# HMC478-SCH.net
KiCad netlist of a schematic drawn in Altium Designer
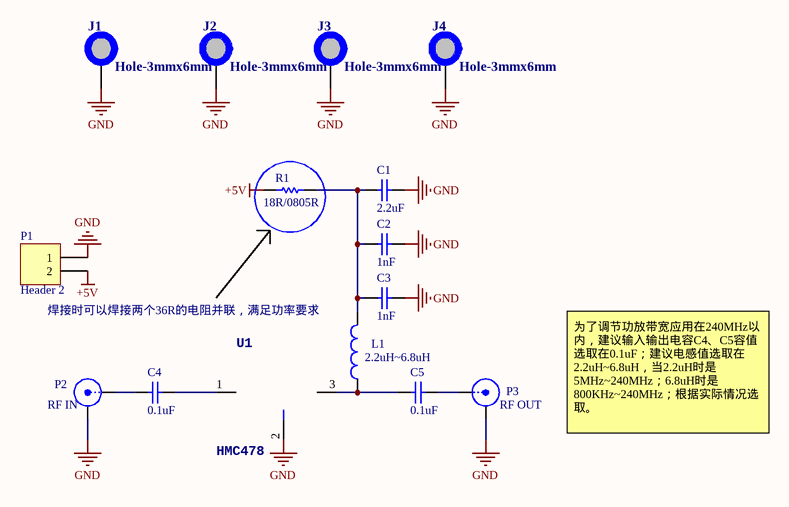
[diagram p0: HMC478-SCH.SchDoc]

(export (version "E")
  (design (tool "Eeschema 10.0.6"))
  (components
    (comp (ref "C1")
      (value "2.2uF")
      (footprint "1206T")
      (description "CAP CER 10000PF 100V X7R 0603")
      (fields
        (field (name "MANUFACTURER") "TDK Corporation")
        (field (name "MANUFACTURER PART NUMBER") "C1608X7R2A103K080AA")
      )
      (libsource (lib "Desiger_Schlib") (part "Cap1"))
    )
    (comp (ref "C2")
      (value "1nF")
      (footprint "0603C")
      (description "CAP CER 10000PF 100V X7R 0603")
      (fields
        (field (name "MANUFACTURER") "TDK Corporation")
        (field (name "MANUFACTURER PART NUMBER") "C1608X7R2A103K080AA")
      )
      (libsource (lib "Desiger_Schlib") (part "Cap1"))
    )
    (comp (ref "C3")
      (value "1nF")
      (footprint "0603C")
      (description "CAP CER 10000PF 100V X7R 0603")
      (fields
        (field (name "MANUFACTURER") "TDK Corporation")
        (field (name "MANUFACTURER PART NUMBER") "C1608X7R2A103K080AA")
      )
      (libsource (lib "Desiger_Schlib") (part "Cap1"))
    )
    (comp (ref "C4")
      (value "0.1uF")
      (footprint "0603C")
      (description "CAP CER 10000PF 100V X7R 0603")
      (fields
        (field (name "MANUFACTURER") "TDK Corporation")
        (field (name "MANUFACTURER PART NUMBER") "C1608X7R2A103K080AA")
      )
      (libsource (lib "Desiger_Schlib") (part "Cap1"))
    )
    (comp (ref "C5")
      (value "0.1uF")
      (footprint "0603C")
      (description "CAP CER 10000PF 100V X7R 0603")
      (fields
        (field (name "MANUFACTURER") "TDK Corporation")
        (field (name "MANUFACTURER PART NUMBER") "C1608X7R2A103K080AA")
      )
      (libsource (lib "Desiger_Schlib") (part "Cap1"))
    )
    (comp (ref "J1")
      (value "Hole-3mmx6mm")
      (footprint "Hole")
      (libsource (lib "Desiger_Schlib") (part "HOLED"))
    )
    (comp (ref "J2")
      (value "Hole-3mmx6mm")
      (footprint "Hole")
      (libsource (lib "Desiger_Schlib") (part "HOLED"))
    )
    (comp (ref "J3")
      (value "Hole-3mmx6mm")
      (footprint "Hole")
      (libsource (lib "Desiger_Schlib") (part "HOLED"))
    )
    (comp (ref "J4")
      (value "Hole-3mmx6mm")
      (footprint "Hole")
      (libsource (lib "Desiger_Schlib") (part "HOLED"))
    )
    (comp (ref "L1")
      (value "2.2uH~6.8uH")
      (footprint "0603L")
      (description "FIXED IND 240NH 4.4A 22MOHM SMD")
      (fields
        (field (name "MANUFACTURER") "Samsung Electro-Mechanics")
        (field (name "MANUFACTURER PART NUMBER") "CIGT201210UHR24MNE")
      )
      (libsource (lib "Desiger_Schlib") (part "Inductors"))
    )
    (comp (ref "P1")
      (value "Header 2")
      (footprint "KF2EDG_3R81_2P")
      (description "Header, 2-Pin")
      (fields (field (name "PUBLISHER") "Altium Limited"))
      (libsource (lib "Miscellaneous Connectors") (part "Header 2"))
    )
    (comp (ref "P2")
      (value "RF IN")
      (footprint "SMA-SMD")
      (description "BNC Elbow Connector")
      (fields (field (name "PUBLISHER") "Altium Limited"))
      (libsource (lib "Miscellaneous Connectors") (part "BNC"))
    )
    (comp (ref "P3")
      (value "RF OUT")
      (footprint "SMA-SMD")
      (description "BNC Elbow Connector")
      (fields (field (name "PUBLISHER") "Altium Limited"))
      (libsource (lib "Miscellaneous Connectors") (part "BNC"))
    )
    (comp (ref "R1")
      (value "18R/0805R")
      (footprint "0805R")
      (description "RES SMD 1K OHM 0.5% 1/16W 0603")
      (fields
        (field (name "MANUFACTURER") "Susumu")
        (field (name "MANUFACTURER PART NUMBER") "RR0816P-102-D")
      )
      (libsource (lib "Desiger_Schlib") (part "Res1"))
    )
    (comp (ref "U1")
      (value "HMC478")
      (footprint "SOT89")
      (description "SiGe HBT GAIN BLOCK  MMIC AMPLIFIER, DC - 4 GHz")
      (libsource (lib "Desiger_Schlib") (part "HMC478"))
    )
  )
  (nets
    (net (code "1") (name "+5V") (class "Default")
      (node (ref "P1") (pin "2") (pinfunction "2_2") (pintype "passive"))
      (node (ref "R1") (pin "1") (pinfunction "1_1") (pintype "passive"))
    )
    (net (code "2") (name "GND") (class "Default")
      (node (ref "C1") (pin "2") (pinfunction "2_2") (pintype "passive"))
      (node (ref "C2") (pin "2") (pinfunction "2_2") (pintype "passive"))
      (node (ref "C3") (pin "2") (pinfunction "2_2") (pintype "passive"))
      (node (ref "J1") (pin "0") (pinfunction "0_0") (pintype "passive"))
      (node (ref "J2") (pin "0") (pinfunction "0_0") (pintype "passive"))
      (node (ref "J3") (pin "0") (pinfunction "0_0") (pintype "passive"))
      (node (ref "J4") (pin "0") (pinfunction "0_0") (pintype "passive"))
      (node (ref "P1") (pin "1") (pinfunction "1_1") (pintype "passive"))
      (node (ref "P2") (pin "2") (pinfunction "Y_2") (pintype "passive"))
      (node (ref "P3") (pin "2") (pinfunction "Y_2") (pintype "passive"))
      (node (ref "U1") (pin "2") (pinfunction "GND_2") (pintype "passive"))
    )
    (net (code "3") (name "Net-(C1-Pad1)") (class "Default")
      (node (ref "C1") (pin "1") (pinfunction "1_1") (pintype "passive"))
      (node (ref "C2") (pin "1") (pinfunction "1_1") (pintype "passive"))
      (node (ref "C3") (pin "1") (pinfunction "1_1") (pintype "passive"))
      (node (ref "L1") (pin "2") (pinfunction "2_2") (pintype "passive"))
      (node (ref "R1") (pin "2") (pinfunction "2_2") (pintype "passive"))
    )
    (net (code "4") (name "Net-(P2-X)") (class "Default")
      (node (ref "C4") (pin "1") (pinfunction "1_1") (pintype "passive"))
      (node (ref "P2") (pin "1") (pinfunction "X_1") (pintype "passive"))
    )
    (net (code "5") (name "Net-(P3-X)") (class "Default")
      (node (ref "C5") (pin "2") (pinfunction "2_2") (pintype "passive"))
      (node (ref "P3") (pin "1") (pinfunction "X_1") (pintype "passive"))
    )
    (net (code "6") (name "Net-(U1-RF_IN)") (class "Default")
      (node (ref "C4") (pin "2") (pinfunction "2_2") (pintype "passive"))
      (node (ref "U1") (pin "1") (pinfunction "RF_IN_1") (pintype "passive"))
    )
    (net (code "7") (name "Net-(U1-RF_OUT)") (class "Default")
      (node (ref "C5") (pin "1") (pinfunction "1_1") (pintype "passive"))
      (node (ref "L1") (pin "1") (pinfunction "1_1") (pintype "passive"))
      (node (ref "U1") (pin "3") (pinfunction "RF_OUT_3") (pintype "passive"))
    )
  )
)
